# Pianissimo.net
KiCad netlist of a schematic drawn in EAGLE
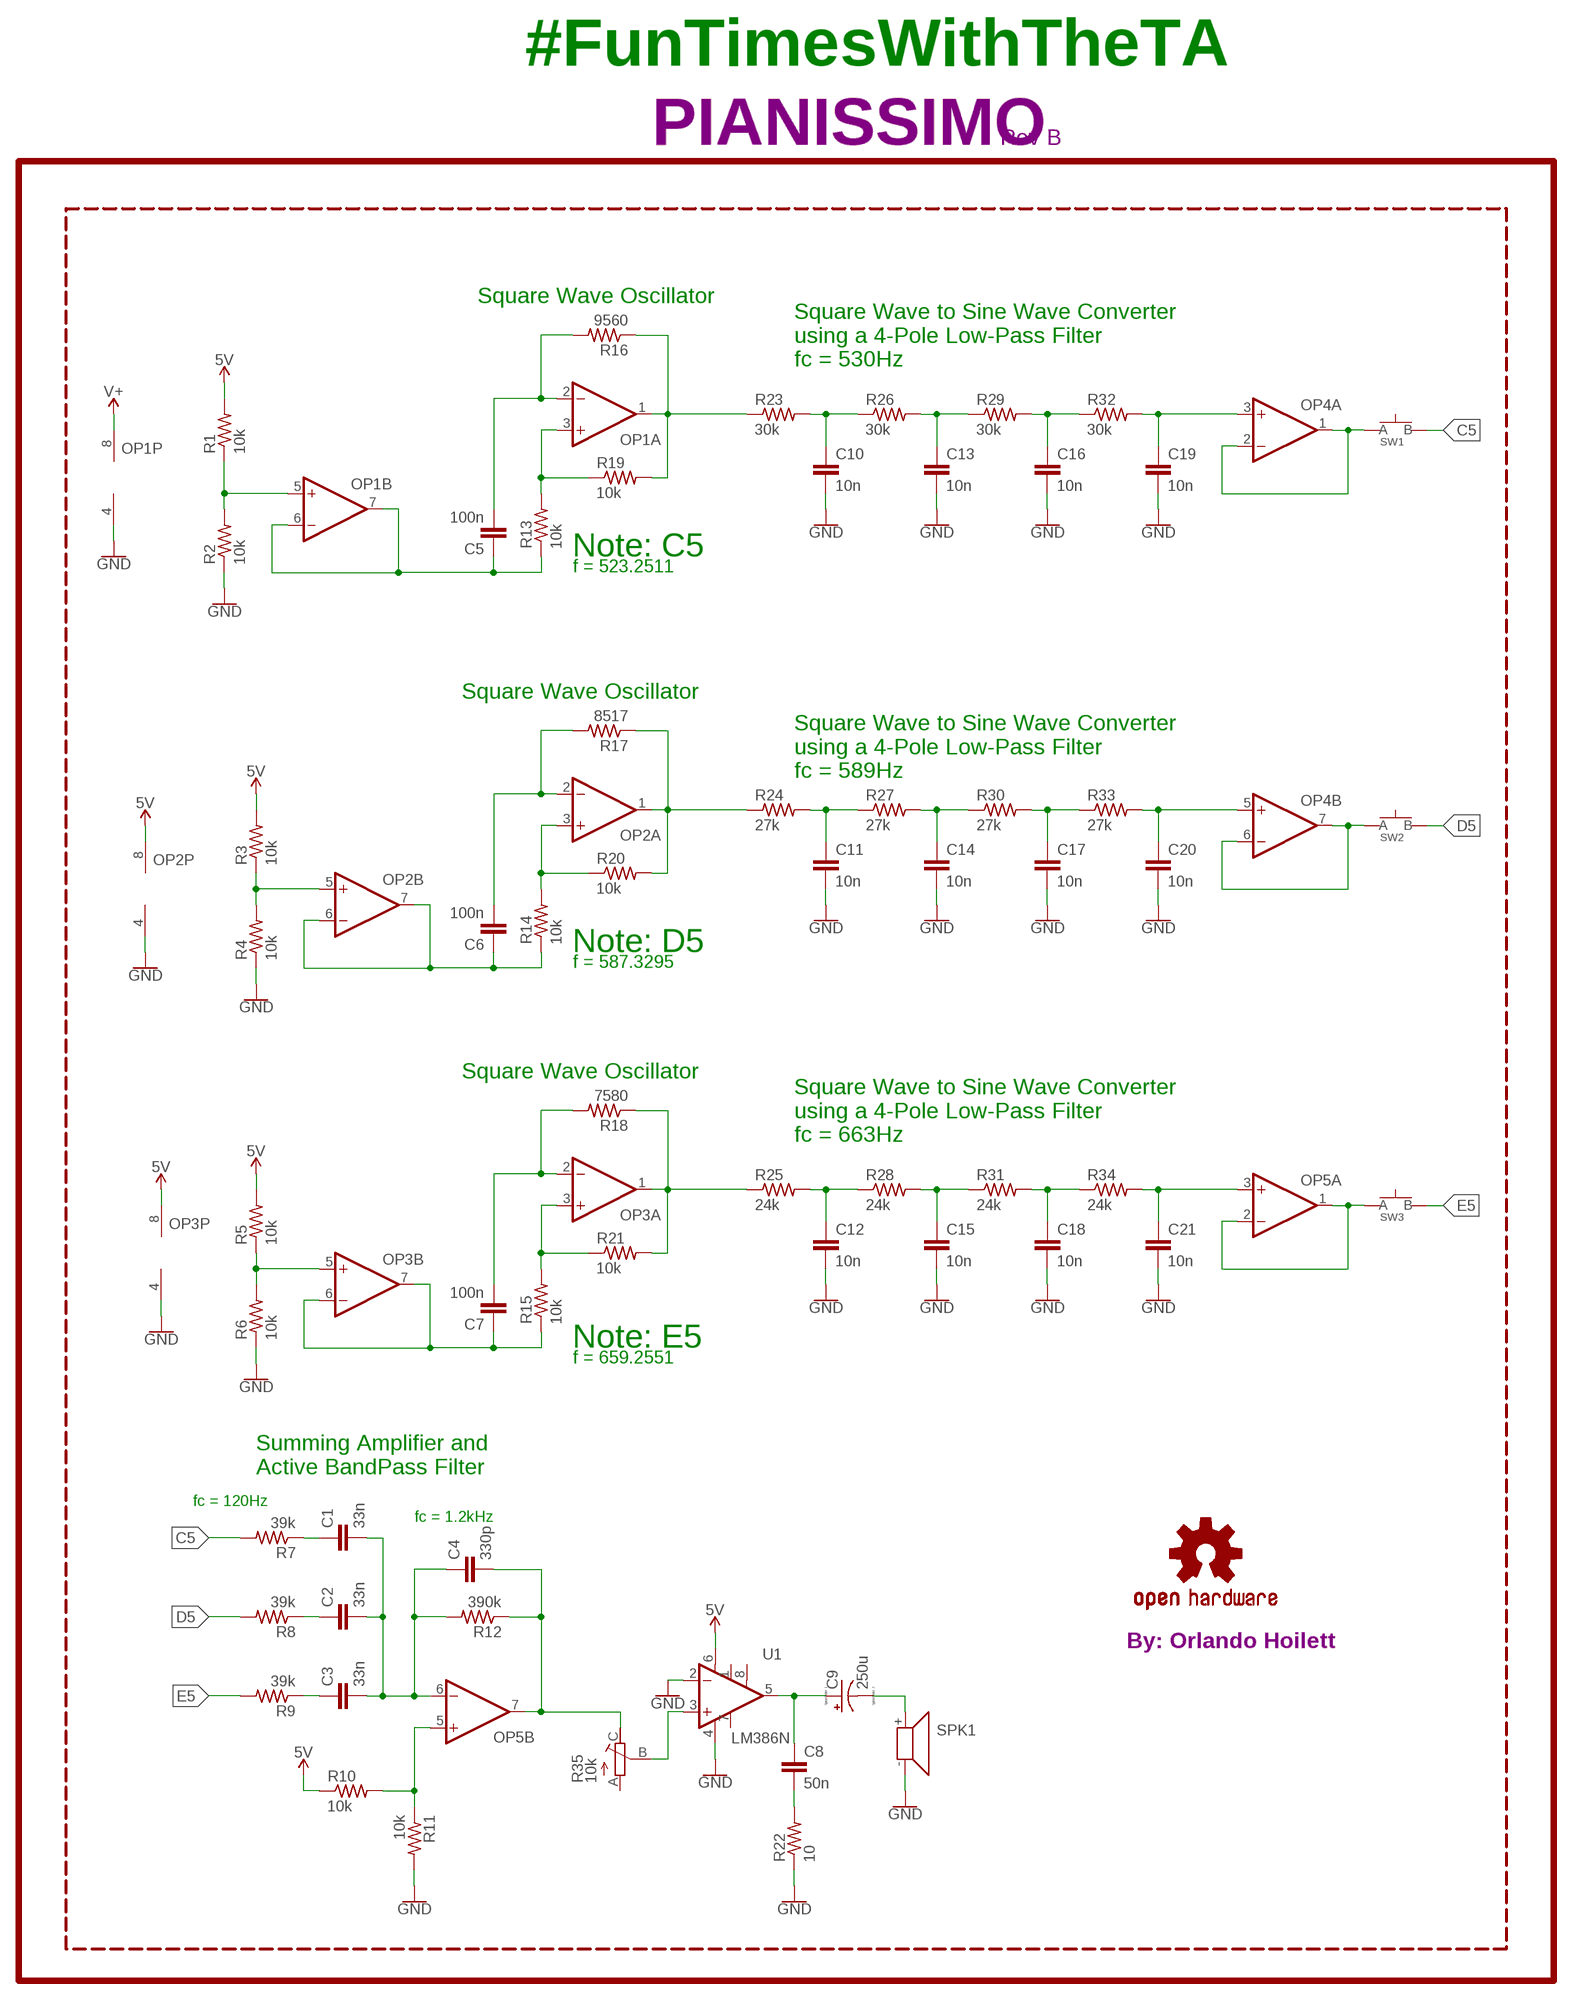
[diagram p0: schematic, sheet 1]

(export (version "E")
  (design (tool "Eeschema 10.0.6"))
  (components
    (comp (ref "C1")
      (value "33n")
      (footprint "eagle-import:C0402")
      (libsource (lib "eagle-import") (part "CAPACITOR0402"))
    )
    (comp (ref "C2")
      (value "33n")
      (footprint "eagle-import:C0402")
      (libsource (lib "eagle-import") (part "CAPACITOR0402"))
    )
    (comp (ref "C3")
      (value "33n")
      (footprint "eagle-import:C0402")
      (libsource (lib "eagle-import") (part "CAPACITOR0402"))
    )
    (comp (ref "C4")
      (value "330p")
      (footprint "eagle-import:C0402")
      (libsource (lib "eagle-import") (part "CAPACITOR0402"))
    )
    (comp (ref "C5")
      (value "100n")
      (footprint "eagle-import:C0402")
      (libsource (lib "eagle-import") (part "CAPACITOR0402"))
    )
    (comp (ref "C6")
      (value "100n")
      (footprint "eagle-import:C0402")
      (libsource (lib "eagle-import") (part "CAPACITOR0402"))
    )
    (comp (ref "C7")
      (value "100n")
      (footprint "eagle-import:C0402")
      (libsource (lib "eagle-import") (part "CAPACITOR0402"))
    )
    (comp (ref "C8")
      (value "50n")
      (footprint "eagle-import:C0603")
      (libsource (lib "eagle-import") (part "CAPACITOR0603"))
    )
    (comp (ref "C9")
      (value "250u")
      (footprint "eagle-import:C-EEU-FM-A-220UF")
      (libsource (lib "eagle-import") (part "CAPACITOR.POLARC-EEU-FM-A-220UF"))
    )
    (comp (ref "C10")
      (value "10n")
      (footprint "eagle-import:C0402")
      (libsource (lib "eagle-import") (part "CAPACITOR0402"))
    )
    (comp (ref "C11")
      (value "10n")
      (footprint "eagle-import:C0402")
      (libsource (lib "eagle-import") (part "CAPACITOR0402"))
    )
    (comp (ref "C12")
      (value "10n")
      (footprint "eagle-import:C0402")
      (libsource (lib "eagle-import") (part "CAPACITOR0402"))
    )
    (comp (ref "C13")
      (value "10n")
      (footprint "eagle-import:C0402")
      (libsource (lib "eagle-import") (part "CAPACITOR0402"))
    )
    (comp (ref "C14")
      (value "10n")
      (footprint "eagle-import:C0402")
      (libsource (lib "eagle-import") (part "CAPACITOR0402"))
    )
    (comp (ref "C15")
      (value "10n")
      (footprint "eagle-import:C0402")
      (libsource (lib "eagle-import") (part "CAPACITOR0402"))
    )
    (comp (ref "C16")
      (value "10n")
      (footprint "eagle-import:C0402")
      (libsource (lib "eagle-import") (part "CAPACITOR0402"))
    )
    (comp (ref "C17")
      (value "10n")
      (footprint "eagle-import:C0402")
      (libsource (lib "eagle-import") (part "CAPACITOR0402"))
    )
    (comp (ref "C18")
      (value "10n")
      (footprint "eagle-import:C0402")
      (libsource (lib "eagle-import") (part "CAPACITOR0402"))
    )
    (comp (ref "C19")
      (value "10n")
      (footprint "eagle-import:C0402")
      (libsource (lib "eagle-import") (part "CAPACITOR0402"))
    )
    (comp (ref "C20")
      (value "10n")
      (footprint "eagle-import:C0402")
      (libsource (lib "eagle-import") (part "CAPACITOR0402"))
    )
    (comp (ref "C21")
      (value "10n")
      (footprint "eagle-import:C0402")
      (libsource (lib "eagle-import") (part "CAPACITOR0402"))
    )
    (comp (ref "LOGO1")
      (value "OSHW-LOGOL")
      (footprint "eagle-import:OSHW-LOGO-L")
      (libsource (lib "eagle-import") (part "OSHW-LOGOL"))
    )
    (comp (ref "OP1")
      (value "OP-DUALR")
      (footprint "eagle-import:SO8")
      (fields (field (name "MPN") "AD8607ARMZ-R2"))
      (libsource (lib "eagle-import") (part "OP-DUALR"))
    )
    (comp (ref "OP2")
      (value "OP-DUALR")
      (footprint "eagle-import:SO8")
      (fields (field (name "MPN") "AD8607ARMZ-R2"))
      (libsource (lib "eagle-import") (part "OP-DUALR"))
    )
    (comp (ref "OP3")
      (value "OP-DUALR")
      (footprint "eagle-import:SO8")
      (fields (field (name "MPN") "AD8607ARMZ-R2"))
      (libsource (lib "eagle-import") (part "OP-DUALR"))
    )
    (comp (ref "OP4")
      (value "OP-DUALR")
      (footprint "eagle-import:SO8")
      (fields (field (name "MPN") "AD8607ARMZ-R2"))
      (libsource (lib "eagle-import") (part "OP-DUALR"))
    )
    (comp (ref "OP5")
      (value "OP-DUALR")
      (footprint "eagle-import:SO8")
      (fields (field (name "MPN") "AD8607ARMZ-R2"))
      (libsource (lib "eagle-import") (part "OP-DUALR"))
    )
    (comp (ref "R1")
      (value "10k")
      (footprint "eagle-import:R0402-SMALL")
      (libsource (lib "eagle-import") (part "RESISTOR0402-SMALLER"))
    )
    (comp (ref "R2")
      (value "10k")
      (footprint "eagle-import:R0402-SMALL")
      (libsource (lib "eagle-import") (part "RESISTOR0402-SMALLER"))
    )
    (comp (ref "R3")
      (value "10k")
      (footprint "eagle-import:R0402-SMALL")
      (libsource (lib "eagle-import") (part "RESISTOR0402-SMALLER"))
    )
    (comp (ref "R4")
      (value "10k")
      (footprint "eagle-import:R0402-SMALL")
      (libsource (lib "eagle-import") (part "RESISTOR0402-SMALLER"))
    )
    (comp (ref "R5")
      (value "10k")
      (footprint "eagle-import:R0402-SMALL")
      (libsource (lib "eagle-import") (part "RESISTOR0402-SMALLER"))
    )
    (comp (ref "R6")
      (value "10k")
      (footprint "eagle-import:R0402-SMALL")
      (libsource (lib "eagle-import") (part "RESISTOR0402-SMALLER"))
    )
    (comp (ref "R7")
      (value "39k")
      (footprint "eagle-import:R0402-SMALL")
      (libsource (lib "eagle-import") (part "RESISTOR0402-SMALLER"))
    )
    (comp (ref "R8")
      (value "39k")
      (footprint "eagle-import:R0402-SMALL")
      (libsource (lib "eagle-import") (part "RESISTOR0402-SMALLER"))
    )
    (comp (ref "R9")
      (value "39k")
      (footprint "eagle-import:R0402-SMALL")
      (libsource (lib "eagle-import") (part "RESISTOR0402-SMALLER"))
    )
    (comp (ref "R10")
      (value "10k")
      (footprint "eagle-import:R0402-SMALL")
      (libsource (lib "eagle-import") (part "RESISTOR0402-SMALLER"))
    )
    (comp (ref "R11")
      (value "10k")
      (footprint "eagle-import:R0402-SMALL")
      (libsource (lib "eagle-import") (part "RESISTOR0402-SMALLER"))
    )
    (comp (ref "R12")
      (value "390k")
      (footprint "eagle-import:R0402-SMALL")
      (libsource (lib "eagle-import") (part "RESISTOR0402-SMALLER"))
    )
    (comp (ref "R13")
      (value "10k")
      (footprint "eagle-import:R0402-SMALL")
      (libsource (lib "eagle-import") (part "RESISTOR0402-SMALLER"))
    )
    (comp (ref "R14")
      (value "10k")
      (footprint "eagle-import:R0402-SMALL")
      (libsource (lib "eagle-import") (part "RESISTOR0402-SMALLER"))
    )
    (comp (ref "R15")
      (value "10k")
      (footprint "eagle-import:R0402-SMALL")
      (libsource (lib "eagle-import") (part "RESISTOR0402-SMALLER"))
    )
    (comp (ref "R16")
      (value "9560")
      (footprint "eagle-import:R0402-SMALL")
      (libsource (lib "eagle-import") (part "RESISTOR0402-SMALLER"))
    )
    (comp (ref "R17")
      (value "8517")
      (footprint "eagle-import:R0402-SMALL")
      (libsource (lib "eagle-import") (part "RESISTOR0402-SMALLER"))
    )
    (comp (ref "R18")
      (value "7580")
      (footprint "eagle-import:R0402-SMALL")
      (libsource (lib "eagle-import") (part "RESISTOR0402-SMALLER"))
    )
    (comp (ref "R19")
      (value "10k")
      (footprint "eagle-import:R0402-SMALL")
      (libsource (lib "eagle-import") (part "RESISTOR0402-SMALLER"))
    )
    (comp (ref "R20")
      (value "10k")
      (footprint "eagle-import:R0402-SMALL")
      (libsource (lib "eagle-import") (part "RESISTOR0402-SMALLER"))
    )
    (comp (ref "R21")
      (value "10k")
      (footprint "eagle-import:R0402-SMALL")
      (libsource (lib "eagle-import") (part "RESISTOR0402-SMALLER"))
    )
    (comp (ref "R22")
      (value "10")
      (footprint "eagle-import:R0603")
      (libsource (lib "eagle-import") (part "RESISTOR0603"))
    )
    (comp (ref "R23")
      (value "30k")
      (footprint "eagle-import:R0402-SMALL")
      (libsource (lib "eagle-import") (part "RESISTOR0402-SMALLER"))
    )
    (comp (ref "R24")
      (value "27k")
      (footprint "eagle-import:R0402-SMALL")
      (libsource (lib "eagle-import") (part "RESISTOR0402-SMALLER"))
    )
    (comp (ref "R25")
      (value "24k")
      (footprint "eagle-import:R0402-SMALL")
      (libsource (lib "eagle-import") (part "RESISTOR0402-SMALLER"))
    )
    (comp (ref "R26")
      (value "30k")
      (footprint "eagle-import:R0402-SMALL")
      (libsource (lib "eagle-import") (part "RESISTOR0402-SMALLER"))
    )
    (comp (ref "R27")
      (value "27k")
      (footprint "eagle-import:R0402-SMALL")
      (libsource (lib "eagle-import") (part "RESISTOR0402-SMALLER"))
    )
    (comp (ref "R28")
      (value "24k")
      (footprint "eagle-import:R0402-SMALL")
      (libsource (lib "eagle-import") (part "RESISTOR0402-SMALLER"))
    )
    (comp (ref "R29")
      (value "30k")
      (footprint "eagle-import:R0402-SMALL")
      (libsource (lib "eagle-import") (part "RESISTOR0402-SMALLER"))
    )
    (comp (ref "R30")
      (value "27k")
      (footprint "eagle-import:R0402-SMALL")
      (libsource (lib "eagle-import") (part "RESISTOR0402-SMALLER"))
    )
    (comp (ref "R31")
      (value "24k")
      (footprint "eagle-import:R0402-SMALL")
      (libsource (lib "eagle-import") (part "RESISTOR0402-SMALLER"))
    )
    (comp (ref "R32")
      (value "30k")
      (footprint "eagle-import:R0402-SMALL")
      (libsource (lib "eagle-import") (part "RESISTOR0402-SMALLER"))
    )
    (comp (ref "R33")
      (value "27k")
      (footprint "eagle-import:R0402-SMALL")
      (libsource (lib "eagle-import") (part "RESISTOR0402-SMALLER"))
    )
    (comp (ref "R34")
      (value "24k")
      (footprint "eagle-import:R0402-SMALL")
      (libsource (lib "eagle-import") (part "RESISTOR0402-SMALLER"))
    )
    (comp (ref "R35")
      (value "10k")
      (footprint "eagle-import:RTRIMCB10")
      (libsource (lib "eagle-import") (part "R-TRIMM-CB10V"))
    )
    (comp (ref "REV1")
      (value "REVISION.B")
      (footprint "eagle-import:REV.B")
      (libsource (lib "eagle-import") (part "REVISION.B"))
    )
    (comp (ref "SPK1")
      (value "SPEAKER")
      (footprint "eagle-import:SOLDER.TABS")
      (libsource (lib "eagle-import") (part "SPEAKER"))
    )
    (comp (ref "SW1")
      (value "SPST.KT11P4SM34LFS")
      (footprint "eagle-import:SPST.KT11P4SM34LFS")
      (libsource (lib "eagle-import") (part "SPST.KT11P4SM34LFS"))
    )
    (comp (ref "SW2")
      (value "SPST.KT11P4SM34LFS")
      (footprint "eagle-import:SPST.KT11P4SM34LFS")
      (libsource (lib "eagle-import") (part "SPST.KT11P4SM34LFS"))
    )
    (comp (ref "SW3")
      (value "SPST.KT11P4SM34LFS")
      (footprint "eagle-import:SPST.KT11P4SM34LFS")
      (libsource (lib "eagle-import") (part "SPST.KT11P4SM34LFS"))
    )
    (comp (ref "U1")
      (value "LM386N")
      (footprint "eagle-import:DIP08")
      (libsource (lib "eagle-import") (part "LM386"))
    )
  )
  (nets
    (net (code "1") (name "5V") (class "Default")
      (node (ref "OP2") (pin "8") (pinfunction "V+_8") (pintype "power_in"))
      (node (ref "OP3") (pin "8") (pinfunction "V+_8") (pintype "power_in"))
      (node (ref "R1") (pin "2") (pinfunction "2_2") (pintype "passive"))
      (node (ref "R10") (pin "1") (pinfunction "1_1") (pintype "passive"))
      (node (ref "R3") (pin "2") (pinfunction "2_2") (pintype "passive"))
      (node (ref "R5") (pin "2") (pinfunction "2_2") (pintype "passive"))
      (node (ref "U1") (pin "6") (pinfunction "V+_6") (pintype "power_in"))
    )
    (net (code "2") (name "C5") (class "Default")
      (node (ref "R7") (pin "2") (pinfunction "2_2") (pintype "passive"))
      (node (ref "SW1") (pin "3") (pinfunction "B_3") (pintype "bidirectional"))
      (node (ref "SW1") (pin "4") (pinfunction "B_4") (pintype "bidirectional"))
    )
    (net (code "3") (name "D5") (class "Default")
      (node (ref "R8") (pin "2") (pinfunction "2_2") (pintype "passive"))
      (node (ref "SW2") (pin "3") (pinfunction "B_3") (pintype "bidirectional"))
      (node (ref "SW2") (pin "4") (pinfunction "B_4") (pintype "bidirectional"))
    )
    (net (code "4") (name "E5") (class "Default")
      (node (ref "R9") (pin "2") (pinfunction "2_2") (pintype "passive"))
      (node (ref "SW3") (pin "3") (pinfunction "B_3") (pintype "bidirectional"))
      (node (ref "SW3") (pin "4") (pinfunction "B_4") (pintype "bidirectional"))
    )
    (net (code "5") (name "GND") (class "Default")
      (node (ref "C10") (pin "2") (pinfunction "2_2") (pintype "passive"))
      (node (ref "C11") (pin "2") (pinfunction "2_2") (pintype "passive"))
      (node (ref "C12") (pin "2") (pinfunction "2_2") (pintype "passive"))
      (node (ref "C13") (pin "2") (pinfunction "2_2") (pintype "passive"))
      (node (ref "C14") (pin "2") (pinfunction "2_2") (pintype "passive"))
      (node (ref "C15") (pin "2") (pinfunction "2_2") (pintype "passive"))
      (node (ref "C16") (pin "2") (pinfunction "2_2") (pintype "passive"))
      (node (ref "C17") (pin "2") (pinfunction "2_2") (pintype "passive"))
      (node (ref "C18") (pin "2") (pinfunction "2_2") (pintype "passive"))
      (node (ref "C19") (pin "2") (pinfunction "2_2") (pintype "passive"))
      (node (ref "C20") (pin "2") (pinfunction "2_2") (pintype "passive"))
      (node (ref "C21") (pin "2") (pinfunction "2_2") (pintype "passive"))
      (node (ref "OP1") (pin "4") (pinfunction "V-_4") (pintype "power_in"))
      (node (ref "OP2") (pin "4") (pinfunction "V-_4") (pintype "power_in"))
      (node (ref "OP3") (pin "4") (pinfunction "V-_4") (pintype "power_in"))
      (node (ref "R11") (pin "2") (pinfunction "2_2") (pintype "passive"))
      (node (ref "R2") (pin "1") (pinfunction "1_1") (pintype "passive"))
      (node (ref "R22") (pin "1") (pinfunction "1_1") (pintype "passive"))
      (node (ref "R4") (pin "1") (pinfunction "1_1") (pintype "passive"))
      (node (ref "R6") (pin "1") (pinfunction "1_1") (pintype "passive"))
      (node (ref "SPK1") (pin "-") (pinfunction "-_-") (pintype "passive"))
      (node (ref "U1") (pin "2") (pinfunction "-IN_2") (pintype "input"))
      (node (ref "U1") (pin "4") (pinfunction "V-_4") (pintype "power_in"))
    )
    (net (code "6") (name "Net-(C1-Pad1)") (class "Default")
      (node (ref "C1") (pin "1") (pinfunction "1_1") (pintype "passive"))
      (node (ref "R7") (pin "1") (pinfunction "1_1") (pintype "passive"))
    )
    (net (code "7") (name "Net-(C2-Pad1)") (class "Default")
      (node (ref "C2") (pin "1") (pinfunction "1_1") (pintype "passive"))
      (node (ref "R8") (pin "1") (pinfunction "1_1") (pintype "passive"))
    )
    (net (code "8") (name "Net-(C3-Pad1)") (class "Default")
      (node (ref "C3") (pin "1") (pinfunction "1_1") (pintype "passive"))
      (node (ref "R9") (pin "1") (pinfunction "1_1") (pintype "passive"))
    )
    (net (code "9") (name "Net-(C8-Pad2)") (class "Default")
      (node (ref "C8") (pin "2") (pinfunction "2_2") (pintype "passive"))
      (node (ref "R22") (pin "2") (pinfunction "2_2") (pintype "passive"))
    )
    (net (code "10") (name "Net-(C9-Pad-)") (class "Default")
      (node (ref "C9") (pin "-") (pinfunction "-_-") (pintype "passive"))
      (node (ref "SPK1") (pin "+") (pinfunction "+_+") (pintype "passive"))
    )
    (net (code "11") (name "Net-(C10-Pad1)") (class "Default")
      (node (ref "C10") (pin "1") (pinfunction "1_1") (pintype "passive"))
      (node (ref "R23") (pin "2") (pinfunction "2_2") (pintype "passive"))
      (node (ref "R26") (pin "1") (pinfunction "1_1") (pintype "passive"))
    )
    (net (code "12") (name "Net-(C11-Pad1)") (class "Default")
      (node (ref "C11") (pin "1") (pinfunction "1_1") (pintype "passive"))
      (node (ref "R24") (pin "2") (pinfunction "2_2") (pintype "passive"))
      (node (ref "R27") (pin "1") (pinfunction "1_1") (pintype "passive"))
    )
    (net (code "13") (name "Net-(C12-Pad1)") (class "Default")
      (node (ref "C12") (pin "1") (pinfunction "1_1") (pintype "passive"))
      (node (ref "R25") (pin "2") (pinfunction "2_2") (pintype "passive"))
      (node (ref "R28") (pin "1") (pinfunction "1_1") (pintype "passive"))
    )
    (net (code "14") (name "Net-(C13-Pad1)") (class "Default")
      (node (ref "C13") (pin "1") (pinfunction "1_1") (pintype "passive"))
      (node (ref "R26") (pin "2") (pinfunction "2_2") (pintype "passive"))
      (node (ref "R29") (pin "1") (pinfunction "1_1") (pintype "passive"))
    )
    (net (code "15") (name "Net-(C14-Pad1)") (class "Default")
      (node (ref "C14") (pin "1") (pinfunction "1_1") (pintype "passive"))
      (node (ref "R27") (pin "2") (pinfunction "2_2") (pintype "passive"))
      (node (ref "R30") (pin "1") (pinfunction "1_1") (pintype "passive"))
    )
    (net (code "16") (name "Net-(C15-Pad1)") (class "Default")
      (node (ref "C15") (pin "1") (pinfunction "1_1") (pintype "passive"))
      (node (ref "R28") (pin "2") (pinfunction "2_2") (pintype "passive"))
      (node (ref "R31") (pin "1") (pinfunction "1_1") (pintype "passive"))
    )
    (net (code "17") (name "Net-(C16-Pad1)") (class "Default")
      (node (ref "C16") (pin "1") (pinfunction "1_1") (pintype "passive"))
      (node (ref "R29") (pin "2") (pinfunction "2_2") (pintype "passive"))
      (node (ref "R32") (pin "1") (pinfunction "1_1") (pintype "passive"))
    )
    (net (code "18") (name "Net-(C17-Pad1)") (class "Default")
      (node (ref "C17") (pin "1") (pinfunction "1_1") (pintype "passive"))
      (node (ref "R30") (pin "2") (pinfunction "2_2") (pintype "passive"))
      (node (ref "R33") (pin "1") (pinfunction "1_1") (pintype "passive"))
    )
    (net (code "19") (name "Net-(C18-Pad1)") (class "Default")
      (node (ref "C18") (pin "1") (pinfunction "1_1") (pintype "passive"))
      (node (ref "R31") (pin "2") (pinfunction "2_2") (pintype "passive"))
      (node (ref "R34") (pin "1") (pinfunction "1_1") (pintype "passive"))
    )
    (net (code "20") (name "Net-(OP1A-+IN)") (class "Default")
      (node (ref "OP1") (pin "3") (pinfunction "+IN_3") (pintype "input"))
      (node (ref "R13") (pin "2") (pinfunction "2_2") (pintype "passive"))
      (node (ref "R19") (pin "1") (pinfunction "1_1") (pintype "passive"))
    )
    (net (code "21") (name "Net-(OP1A--IN)") (class "Default")
      (node (ref "C5") (pin "2") (pinfunction "2_2") (pintype "passive"))
      (node (ref "OP1") (pin "2") (pinfunction "-IN_2") (pintype "input"))
      (node (ref "R16") (pin "2") (pinfunction "2_2") (pintype "passive"))
    )
    (net (code "22") (name "Net-(OP1A-OUT)") (class "Default")
      (node (ref "OP1") (pin "1") (pinfunction "OUT_1") (pintype "output"))
      (node (ref "R16") (pin "1") (pinfunction "1_1") (pintype "passive"))
      (node (ref "R19") (pin "2") (pinfunction "2_2") (pintype "passive"))
      (node (ref "R23") (pin "1") (pinfunction "1_1") (pintype "passive"))
    )
    (net (code "23") (name "Net-(OP1B-+IN)") (class "Default")
      (node (ref "OP1") (pin "5") (pinfunction "+IN_5") (pintype "input"))
      (node (ref "R1") (pin "1") (pinfunction "1_1") (pintype "passive"))
      (node (ref "R2") (pin "2") (pinfunction "2_2") (pintype "passive"))
    )
    (net (code "24") (name "Net-(OP1B--IN)") (class "Default")
      (node (ref "C5") (pin "1") (pinfunction "1_1") (pintype "passive"))
      (node (ref "OP1") (pin "6") (pinfunction "-IN_6") (pintype "input"))
      (node (ref "OP1") (pin "7") (pinfunction "OUT_7") (pintype "output"))
      (node (ref "R13") (pin "1") (pinfunction "1_1") (pintype "passive"))
    )
    (net (code "25") (name "Net-(OP2A-+IN)") (class "Default")
      (node (ref "OP2") (pin "3") (pinfunction "+IN_3") (pintype "input"))
      (node (ref "R14") (pin "2") (pinfunction "2_2") (pintype "passive"))
      (node (ref "R20") (pin "1") (pinfunction "1_1") (pintype "passive"))
    )
    (net (code "26") (name "Net-(OP2A--IN)") (class "Default")
      (node (ref "C6") (pin "2") (pinfunction "2_2") (pintype "passive"))
      (node (ref "OP2") (pin "2") (pinfunction "-IN_2") (pintype "input"))
      (node (ref "R17") (pin "2") (pinfunction "2_2") (pintype "passive"))
    )
    (net (code "27") (name "Net-(OP2A-OUT)") (class "Default")
      (node (ref "OP2") (pin "1") (pinfunction "OUT_1") (pintype "output"))
      (node (ref "R17") (pin "1") (pinfunction "1_1") (pintype "passive"))
      (node (ref "R20") (pin "2") (pinfunction "2_2") (pintype "passive"))
      (node (ref "R24") (pin "1") (pinfunction "1_1") (pintype "passive"))
    )
    (net (code "28") (name "Net-(OP2B-+IN)") (class "Default")
      (node (ref "OP2") (pin "5") (pinfunction "+IN_5") (pintype "input"))
      (node (ref "R3") (pin "1") (pinfunction "1_1") (pintype "passive"))
      (node (ref "R4") (pin "2") (pinfunction "2_2") (pintype "passive"))
    )
    (net (code "29") (name "Net-(OP2B--IN)") (class "Default")
      (node (ref "C6") (pin "1") (pinfunction "1_1") (pintype "passive"))
      (node (ref "OP2") (pin "6") (pinfunction "-IN_6") (pintype "input"))
      (node (ref "OP2") (pin "7") (pinfunction "OUT_7") (pintype "output"))
      (node (ref "R14") (pin "1") (pinfunction "1_1") (pintype "passive"))
    )
    (net (code "30") (name "Net-(OP3A-+IN)") (class "Default")
      (node (ref "OP3") (pin "3") (pinfunction "+IN_3") (pintype "input"))
      (node (ref "R15") (pin "2") (pinfunction "2_2") (pintype "passive"))
      (node (ref "R21") (pin "1") (pinfunction "1_1") (pintype "passive"))
    )
    (net (code "31") (name "Net-(OP3A--IN)") (class "Default")
      (node (ref "C7") (pin "2") (pinfunction "2_2") (pintype "passive"))
      (node (ref "OP3") (pin "2") (pinfunction "-IN_2") (pintype "input"))
      (node (ref "R18") (pin "2") (pinfunction "2_2") (pintype "passive"))
    )
    (net (code "32") (name "Net-(OP3A-OUT)") (class "Default")
      (node (ref "OP3") (pin "1") (pinfunction "OUT_1") (pintype "output"))
      (node (ref "R18") (pin "1") (pinfunction "1_1") (pintype "passive"))
      (node (ref "R21") (pin "2") (pinfunction "2_2") (pintype "passive"))
      (node (ref "R25") (pin "1") (pinfunction "1_1") (pintype "passive"))
    )
    (net (code "33") (name "Net-(OP3B-+IN)") (class "Default")
      (node (ref "OP3") (pin "5") (pinfunction "+IN_5") (pintype "input"))
      (node (ref "R5") (pin "1") (pinfunction "1_1") (pintype "passive"))
      (node (ref "R6") (pin "2") (pinfunction "2_2") (pintype "passive"))
    )
    (net (code "34") (name "Net-(OP3B--IN)") (class "Default")
      (node (ref "C7") (pin "1") (pinfunction "1_1") (pintype "passive"))
      (node (ref "OP3") (pin "6") (pinfunction "-IN_6") (pintype "input"))
      (node (ref "OP3") (pin "7") (pinfunction "OUT_7") (pintype "output"))
      (node (ref "R15") (pin "1") (pinfunction "1_1") (pintype "passive"))
    )
    (net (code "35") (name "Net-(OP4A-+IN)") (class "Default")
      (node (ref "C19") (pin "1") (pinfunction "1_1") (pintype "passive"))
      (node (ref "OP4") (pin "3") (pinfunction "+IN_3") (pintype "input"))
      (node (ref "R32") (pin "2") (pinfunction "2_2") (pintype "passive"))
    )
    (net (code "36") (name "Net-(OP4A--IN)") (class "Default")
      (node (ref "OP4") (pin "1") (pinfunction "OUT_1") (pintype "output"))
      (node (ref "OP4") (pin "2") (pinfunction "-IN_2") (pintype "input"))
      (node (ref "SW1") (pin "1") (pinfunction "A_1") (pintype "bidirectional"))
      (node (ref "SW1") (pin "2") (pinfunction "A_2") (pintype "bidirectional"))
    )
    (net (code "37") (name "Net-(OP4B-+IN)") (class "Default")
      (node (ref "C20") (pin "1") (pinfunction "1_1") (pintype "passive"))
      (node (ref "OP4") (pin "5") (pinfunction "+IN_5") (pintype "input"))
      (node (ref "R33") (pin "2") (pinfunction "2_2") (pintype "passive"))
    )
    (net (code "38") (name "Net-(OP4B--IN)") (class "Default")
      (node (ref "OP4") (pin "6") (pinfunction "-IN_6") (pintype "input"))
      (node (ref "OP4") (pin "7") (pinfunction "OUT_7") (pintype "output"))
      (node (ref "SW2") (pin "1") (pinfunction "A_1") (pintype "bidirectional"))
      (node (ref "SW2") (pin "2") (pinfunction "A_2") (pintype "bidirectional"))
    )
    (net (code "39") (name "Net-(OP5A-+IN)") (class "Default")
      (node (ref "C21") (pin "1") (pinfunction "1_1") (pintype "passive"))
      (node (ref "OP5") (pin "3") (pinfunction "+IN_3") (pintype "input"))
      (node (ref "R34") (pin "2") (pinfunction "2_2") (pintype "passive"))
    )
    (net (code "40") (name "Net-(OP5A--IN)") (class "Default")
      (node (ref "OP5") (pin "1") (pinfunction "OUT_1") (pintype "output"))
      (node (ref "OP5") (pin "2") (pinfunction "-IN_2") (pintype "input"))
      (node (ref "SW3") (pin "1") (pinfunction "A_1") (pintype "bidirectional"))
      (node (ref "SW3") (pin "2") (pinfunction "A_2") (pintype "bidirectional"))
    )
    (net (code "41") (name "Net-(OP5B-+IN)") (class "Default")
      (node (ref "OP5") (pin "5") (pinfunction "+IN_5") (pintype "input"))
      (node (ref "R10") (pin "2") (pinfunction "2_2") (pintype "passive"))
      (node (ref "R11") (pin "1") (pinfunction "1_1") (pintype "passive"))
    )
    (net (code "42") (name "Net-(OP5B--IN)") (class "Default")
      (node (ref "C1") (pin "2") (pinfunction "2_2") (pintype "passive"))
      (node (ref "C2") (pin "2") (pinfunction "2_2") (pintype "passive"))
      (node (ref "C3") (pin "2") (pinfunction "2_2") (pintype "passive"))
      (node (ref "C4") (pin "1") (pinfunction "1_1") (pintype "passive"))
      (node (ref "OP5") (pin "6") (pinfunction "-IN_6") (pintype "input"))
      (node (ref "R12") (pin "2") (pinfunction "2_2") (pintype "passive"))
    )
    (net (code "43") (name "Net-(OP5B-OUT)") (class "Default")
      (node (ref "C4") (pin "2") (pinfunction "2_2") (pintype "passive"))
      (node (ref "OP5") (pin "7") (pinfunction "OUT_7") (pintype "output"))
      (node (ref "R12") (pin "1") (pinfunction "1_1") (pintype "passive"))
      (node (ref "R35") (pin "C") (pinfunction "E_C") (pintype "passive"))
    )
    (net (code "44") (name "Net-(R35-S)") (class "Default")
      (node (ref "R35") (pin "B") (pinfunction "S_B") (pintype "passive"))
      (node (ref "U1") (pin "3") (pinfunction "+IN_3") (pintype "input"))
    )
    (net (code "45") (name "Net-(U1-OUT)") (class "Default")
      (node (ref "C8") (pin "1") (pinfunction "1_1") (pintype "passive"))
      (node (ref "C9") (pin "+") (pinfunction "+_+") (pintype "passive"))
      (node (ref "U1") (pin "5") (pinfunction "OUT_5") (pintype "output"))
    )
    (net (code "46") (name "V+") (class "Default")
      (node (ref "OP1") (pin "8") (pinfunction "V+_8") (pintype "power_in"))
    )
    (net (code "47") (name "unconnected-(R35-PadA)") (class "Default")
      (node (ref "R35") (pin "A") (pinfunction "A_A") (pintype "passive"))
    )
    (net (code "48") (name "unconnected-(U1-BP-Pad7)") (class "Default")
      (node (ref "U1") (pin "7") (pinfunction "BP_7") (pintype "bidirectional"))
    )
    (net (code "49") (name "unconnected-(U1-GAIN-Pad1)") (class "Default")
      (node (ref "U1") (pin "1") (pinfunction "GAIN_1") (pintype "bidirectional"))
    )
    (net (code "50") (name "unconnected-(U1-GAIN-Pad8)") (class "Default")
      (node (ref "U1") (pin "8") (pinfunction "GAIN_8") (pintype "bidirectional"))
    )
  )
)
